# NEECDUINO_V22.net
KiCad netlist of a schematic drawn in EAGLE
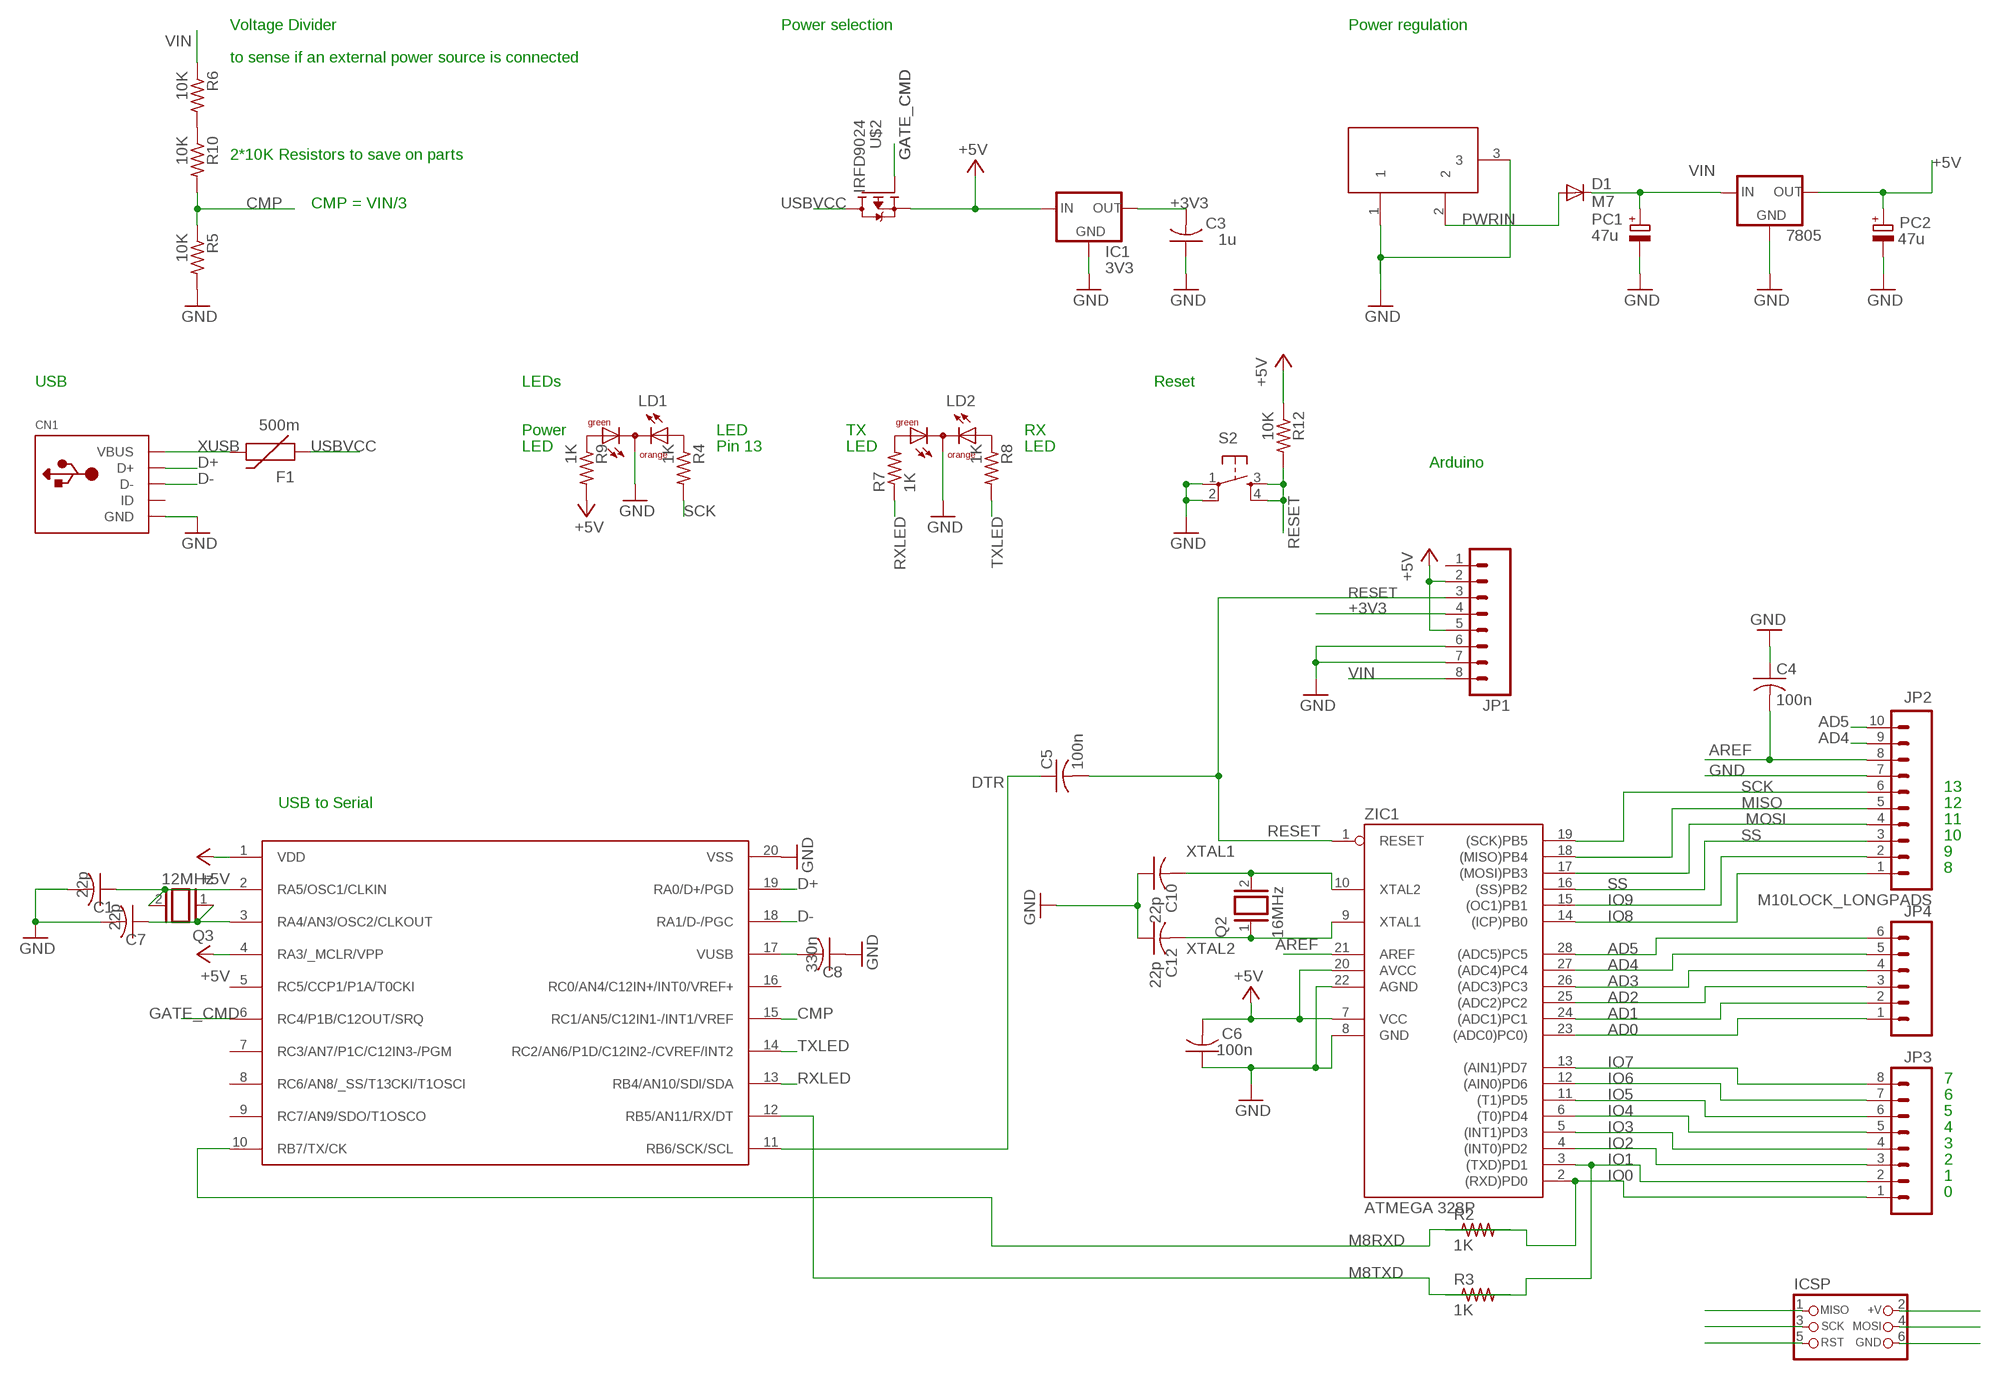
[diagram p0: schematic, sheet 1]

(export (version "E")
  (design (tool "Eeschema 10.0.6"))
  (components
    (comp (ref "7805")
      (value "78XXL")
      (footprint "eagle-import:78XXL")
      (libsource (lib "eagle-import") (part "78XXL"))
    )
    (comp (ref "C1")
      (value "22p")
      (footprint "eagle-import:C025-025X050")
      (libsource (lib "eagle-import") (part "C-US025-025X050"))
    )
    (comp (ref "C3")
      (value "1u")
      (footprint "eagle-import:C050-024X044")
      (libsource (lib "eagle-import") (part "C-US050-024X044"))
    )
    (comp (ref "C4")
      (value "100n")
      (footprint "eagle-import:C025-025X050")
      (libsource (lib "eagle-import") (part "C-US025-025X050"))
    )
    (comp (ref "C5")
      (value "100n")
      (footprint "eagle-import:C025-025X050")
      (libsource (lib "eagle-import") (part "C-US025-025X050"))
    )
    (comp (ref "C6")
      (value "100n")
      (footprint "eagle-import:C025-025X050")
      (libsource (lib "eagle-import") (part "C-US025-025X050"))
    )
    (comp (ref "C7")
      (value "22p")
      (footprint "eagle-import:C025-025X050")
      (libsource (lib "eagle-import") (part "C-US025-025X050"))
    )
    (comp (ref "C8")
      (value "330n")
      (footprint "eagle-import:C025-025X050")
      (libsource (lib "eagle-import") (part "C-US025-025X050"))
    )
    (comp (ref "C10")
      (value "22p")
      (footprint "eagle-import:C025-025X050")
      (libsource (lib "eagle-import") (part "C-US025-025X050"))
    )
    (comp (ref "C12")
      (value "22p")
      (footprint "eagle-import:C025-025X050")
      (libsource (lib "eagle-import") (part "C-US025-025X050"))
    )
    (comp (ref "CN1")
      (value "USBMOLEX")
      (footprint "eagle-import:USB-MINIB-THM-MOLEX")
      (libsource (lib "eagle-import") (part "USBMOLEX"))
    )
    (comp (ref "D1")
      (value "M7")
      (footprint "eagle-import:D-10")
      (libsource (lib "eagle-import") (part "DIODE-D-10"))
    )
    (comp (ref "F1")
      (value "500m")
      (footprint "eagle-import:PTC")
      (libsource (lib "eagle-import") (part "PTCPTH"))
    )
    (comp (ref "IC1")
      (value "3V3")
      (footprint "eagle-import:TO92-INLINE")
      (libsource (lib "eagle-import") (part "LP2950?"))
    )
    (comp (ref "ICSP")
      (value "CON_HEADER_PRG_AVR_ICSP")
      (footprint "eagle-import:HEADER_PRG_2X03")
      (libsource (lib "eagle-import") (part "CON_HEADER_PRG_AVR_ICSP"))
    )
    (comp (ref "JP1")
      (value "M08LOCK_LONGPADS")
      (footprint "eagle-import:1X08_LOCK_LONGPADS")
      (libsource (lib "eagle-import") (part "M08LOCK_LONGPADS"))
    )
    (comp (ref "JP2")
      (value "M10LOCK_LONGPADS")
      (footprint "eagle-import:1X10_LOCK_LONGPADS")
      (libsource (lib "eagle-import") (part "M10LOCK_LONGPADS"))
    )
    (comp (ref "JP3")
      (value "M08LOCK_LONGPADS")
      (footprint "eagle-import:1X08_LOCK_LONGPADS")
      (libsource (lib "eagle-import") (part "M08LOCK_LONGPADS"))
    )
    (comp (ref "JP4")
      (value "M06LOCK_LONGPADS")
      (footprint "eagle-import:1X06_LOCK_LONGPADS")
      (libsource (lib "eagle-import") (part "M06LOCK_LONGPADS"))
    )
    (comp (ref "LD1")
      (value "DUOLED-GO-C")
      (footprint "eagle-import:DUOLED-C-3MM")
      (libsource (lib "eagle-import") (part "DUOLED-GO-C"))
    )
    (comp (ref "LD2")
      (value "DUOLED-GO-C")
      (footprint "eagle-import:DUOLED-C-3MM")
      (libsource (lib "eagle-import") (part "DUOLED-GO-C"))
    )
    (comp (ref "PC1")
      (value "47u")
      (footprint "eagle-import:E2,5-5")
      (libsource (lib "eagle-import") (part "CPOL-EUE2.5-5"))
    )
    (comp (ref "PC2")
      (value "47u")
      (footprint "eagle-import:E2,5-5")
      (libsource (lib "eagle-import") (part "CPOL-EUE2.5-5"))
    )
    (comp (ref "Q2")
      (value "16MHz")
      (footprint "eagle-import:QS")
      (libsource (lib "eagle-import") (part "XTAL/S"))
    )
    (comp (ref "Q3")
      (value "12MHz")
      (footprint "eagle-import:QS")
      (libsource (lib "eagle-import") (part "XTAL/S"))
    )
    (comp (ref "R2")
      (value "1K")
      (footprint "eagle-import:0204_5")
      (libsource (lib "eagle-import") (part "R-US_0204/5"))
    )
    (comp (ref "R3")
      (value "1K")
      (footprint "eagle-import:0204_5")
      (libsource (lib "eagle-import") (part "R-US_0204/5"))
    )
    (comp (ref "R4")
      (value "1K")
      (footprint "eagle-import:0204_5")
      (libsource (lib "eagle-import") (part "R-US_0204/5"))
    )
    (comp (ref "R5")
      (value "10K")
      (footprint "eagle-import:0204_5")
      (libsource (lib "eagle-import") (part "R-US_0204/5"))
    )
    (comp (ref "R6")
      (value "10K")
      (footprint "eagle-import:0204_5")
      (libsource (lib "eagle-import") (part "R-US_0204/5"))
    )
    (comp (ref "R7")
      (value "1K")
      (footprint "eagle-import:0204_5")
      (libsource (lib "eagle-import") (part "R-US_0204/5"))
    )
    (comp (ref "R8")
      (value "1K")
      (footprint "eagle-import:0204_5")
      (libsource (lib "eagle-import") (part "R-US_0204/5"))
    )
    (comp (ref "R9")
      (value "1K")
      (footprint "eagle-import:0204_5")
      (libsource (lib "eagle-import") (part "R-US_0204/5"))
    )
    (comp (ref "R10")
      (value "10K")
      (footprint "eagle-import:0204_5")
      (libsource (lib "eagle-import") (part "R-US_0204/5"))
    )
    (comp (ref "R12")
      (value "10K")
      (footprint "eagle-import:0204_5")
      (libsource (lib "eagle-import") (part "R-US_0204/5"))
    )
    (comp (ref "S2")
      (value "TAC_SWITCHPTH")
      (footprint "eagle-import:TACTILE-PTH")
      (libsource (lib "eagle-import") (part "TAC_SWITCHPTH"))
    )
    (comp (ref "U$1")
      (value "PIC18F14K50")
      (footprint "eagle-import:DIL20")
      (libsource (lib "eagle-import") (part "PIC18XF1XK50"))
    )
    (comp (ref "U$2")
      (value "IRFD9024")
      (footprint "eagle-import:DIL04")
      (libsource (lib "eagle-import") (part "IRFD9024"))
    )
    (comp (ref "X1")
      (value "DC21MMX")
      (footprint "eagle-import:DC-21MM")
      (libsource (lib "eagle-import") (part "DC21MMX"))
    )
    (comp (ref "ZIC1")
      (value "ATMEGA 328P")
      (footprint "eagle-import:DIL28-3")
      (libsource (lib "eagle-import") (part "AT90S4433P"))
    )
  )
  (nets
    (net (code "1") (name "+5V") (class "Default")
      (node (ref "7805") (pin "OUT") (pinfunction "OUT_OUT") (pintype "passive"))
      (node (ref "C6") (pin "2") (pinfunction "2_2") (pintype "passive"))
      (node (ref "IC1") (pin "3") (pinfunction "IN_3") (pintype "input"))
      (node (ref "ICSP") (pin "2") (pinfunction "+V_2") (pintype "passive"))
      (node (ref "JP1") (pin "2") (pinfunction "2_2") (pintype "passive"))
      (node (ref "JP1") (pin "5") (pinfunction "5_5") (pintype "passive"))
      (node (ref "PC2") (pin "+") (pinfunction "+_+") (pintype "passive"))
      (node (ref "R12") (pin "1") (pinfunction "1_1") (pintype "passive"))
      (node (ref "R9") (pin "2") (pinfunction "2_2") (pintype "passive"))
      (node (ref "U$1") (pin "1") (pinfunction "VDD_1") (pintype "power_in"))
      (node (ref "U$1") (pin "4") (pinfunction "RA3/_MCLR/VPP_4") (pintype "bidirectional"))
      (node (ref "U$2") (pin "4") (pinfunction "S_4") (pintype "passive"))
      (node (ref "ZIC1") (pin "20") (pinfunction "AVCC_20") (pintype "power_in"))
      (node (ref "ZIC1") (pin "7") (pinfunction "VCC_7") (pintype "power_in"))
    )
    (net (code "2") (name "/+3V3") (class "Default")
      (node (ref "C3") (pin "2") (pinfunction "2_2") (pintype "passive"))
      (node (ref "IC1") (pin "1") (pinfunction "OUT_1") (pintype "passive"))
      (node (ref "JP1") (pin "4") (pinfunction "4_4") (pintype "passive"))
    )
    (net (code "3") (name "/AD0") (class "Default")
      (node (ref "JP4") (pin "1") (pinfunction "1_1") (pintype "passive"))
      (node (ref "ZIC1") (pin "23") (pinfunction "(ADC0)PC0)_23") (pintype "bidirectional"))
    )
    (net (code "4") (name "/AD1") (class "Default")
      (node (ref "JP4") (pin "2") (pinfunction "2_2") (pintype "passive"))
      (node (ref "ZIC1") (pin "24") (pinfunction "(ADC1)PC1_24") (pintype "bidirectional"))
    )
    (net (code "5") (name "/AD2") (class "Default")
      (node (ref "JP4") (pin "3") (pinfunction "3_3") (pintype "passive"))
      (node (ref "ZIC1") (pin "25") (pinfunction "(ADC2)PC2_25") (pintype "bidirectional"))
    )
    (net (code "6") (name "/AD3") (class "Default")
      (node (ref "JP4") (pin "4") (pinfunction "4_4") (pintype "passive"))
      (node (ref "ZIC1") (pin "26") (pinfunction "(ADC3)PC3_26") (pintype "bidirectional"))
    )
    (net (code "7") (name "/AD4") (class "Default")
      (node (ref "JP2") (pin "9") (pinfunction "9_9") (pintype "passive"))
      (node (ref "JP4") (pin "5") (pinfunction "5_5") (pintype "passive"))
      (node (ref "ZIC1") (pin "27") (pinfunction "(ADC4)PC4_27") (pintype "bidirectional"))
    )
    (net (code "8") (name "/AD5") (class "Default")
      (node (ref "JP2") (pin "10") (pinfunction "10_10") (pintype "passive"))
      (node (ref "JP4") (pin "6") (pinfunction "6_6") (pintype "passive"))
      (node (ref "ZIC1") (pin "28") (pinfunction "(ADC5)PC5_28") (pintype "bidirectional"))
    )
    (net (code "9") (name "/AREF") (class "Default")
      (node (ref "C4") (pin "2") (pinfunction "2_2") (pintype "passive"))
      (node (ref "JP2") (pin "8") (pinfunction "8_8") (pintype "passive"))
      (node (ref "ZIC1") (pin "21") (pinfunction "AREF_21") (pintype "passive"))
    )
    (net (code "10") (name "/CMP") (class "Default")
      (node (ref "R10") (pin "2") (pinfunction "2_2") (pintype "passive"))
      (node (ref "R5") (pin "1") (pinfunction "1_1") (pintype "passive"))
      (node (ref "U$1") (pin "15") (pinfunction "RC1/AN5/C12IN1-/INT1/VREF_15") (pintype "bidirectional"))
    )
    (net (code "11") (name "/D+") (class "Default")
      (node (ref "CN1") (pin "D+") (pinfunction "D+_D+") (pintype "bidirectional"))
      (node (ref "U$1") (pin "19") (pinfunction "RA0/D+/PGD_19") (pintype "bidirectional"))
    )
    (net (code "12") (name "/D-") (class "Default")
      (node (ref "CN1") (pin "D-") (pinfunction "D-_D-") (pintype "bidirectional"))
      (node (ref "U$1") (pin "18") (pinfunction "RA1/D-/PGC_18") (pintype "bidirectional"))
    )
    (net (code "13") (name "/DTR") (class "Default")
      (node (ref "C5") (pin "1") (pinfunction "1_1") (pintype "passive"))
      (node (ref "U$1") (pin "11") (pinfunction "RB6/SCK/SCL_11") (pintype "bidirectional"))
    )
    (net (code "14") (name "/GATE_CMD") (class "Default")
      (node (ref "U$1") (pin "6") (pinfunction "RC4/P1B/C12OUT/SRQ_6") (pintype "bidirectional"))
      (node (ref "U$2") (pin "3") (pinfunction "G_3") (pintype "passive"))
    )
    (net (code "15") (name "/IO0") (class "Default")
      (node (ref "JP3") (pin "1") (pinfunction "1_1") (pintype "passive"))
      (node (ref "R2") (pin "1") (pinfunction "1_1") (pintype "passive"))
      (node (ref "ZIC1") (pin "2") (pinfunction "(RXD)PD0_2") (pintype "bidirectional"))
    )
    (net (code "16") (name "/IO1") (class "Default")
      (node (ref "JP3") (pin "2") (pinfunction "2_2") (pintype "passive"))
      (node (ref "R3") (pin "1") (pinfunction "1_1") (pintype "passive"))
      (node (ref "ZIC1") (pin "3") (pinfunction "(TXD)PD1_3") (pintype "bidirectional"))
    )
    (net (code "17") (name "/IO2") (class "Default")
      (node (ref "JP3") (pin "3") (pinfunction "3_3") (pintype "passive"))
      (node (ref "ZIC1") (pin "4") (pinfunction "(INT0)PD2_4") (pintype "bidirectional"))
    )
    (net (code "18") (name "/IO3") (class "Default")
      (node (ref "JP3") (pin "4") (pinfunction "4_4") (pintype "passive"))
      (node (ref "ZIC1") (pin "5") (pinfunction "(INT1)PD3_5") (pintype "bidirectional"))
    )
    (net (code "19") (name "/IO4") (class "Default")
      (node (ref "JP3") (pin "5") (pinfunction "5_5") (pintype "passive"))
      (node (ref "ZIC1") (pin "6") (pinfunction "(T0)PD4_6") (pintype "bidirectional"))
    )
    (net (code "20") (name "/IO5") (class "Default")
      (node (ref "JP3") (pin "6") (pinfunction "6_6") (pintype "passive"))
      (node (ref "ZIC1") (pin "11") (pinfunction "(T1)PD5_11") (pintype "bidirectional"))
    )
    (net (code "21") (name "/IO6") (class "Default")
      (node (ref "JP3") (pin "7") (pinfunction "7_7") (pintype "passive"))
      (node (ref "ZIC1") (pin "12") (pinfunction "(AIN0)PD6_12") (pintype "bidirectional"))
    )
    (net (code "22") (name "/IO7") (class "Default")
      (node (ref "JP3") (pin "8") (pinfunction "8_8") (pintype "passive"))
      (node (ref "ZIC1") (pin "13") (pinfunction "(AIN1)PD7_13") (pintype "bidirectional"))
    )
    (net (code "23") (name "/IO8") (class "Default")
      (node (ref "JP2") (pin "1") (pinfunction "1_1") (pintype "passive"))
      (node (ref "ZIC1") (pin "14") (pinfunction "(ICP)PB0_14") (pintype "bidirectional"))
    )
    (net (code "24") (name "/IO9") (class "Default")
      (node (ref "JP2") (pin "2") (pinfunction "2_2") (pintype "passive"))
      (node (ref "ZIC1") (pin "15") (pinfunction "(OC1)PB1_15") (pintype "bidirectional"))
    )
    (net (code "25") (name "/M8RXD") (class "Default")
      (node (ref "R2") (pin "2") (pinfunction "2_2") (pintype "passive"))
      (node (ref "U$1") (pin "10") (pinfunction "RB7/TX/CK_10") (pintype "bidirectional"))
    )
    (net (code "26") (name "/M8TXD") (class "Default")
      (node (ref "R3") (pin "2") (pinfunction "2_2") (pintype "passive"))
      (node (ref "U$1") (pin "12") (pinfunction "RB5/AN11/RX/DT_12") (pintype "bidirectional"))
    )
    (net (code "27") (name "/MISO") (class "Default")
      (node (ref "ICSP") (pin "1") (pinfunction "MISO_1") (pintype "passive"))
      (node (ref "JP2") (pin "5") (pinfunction "5_5") (pintype "passive"))
      (node (ref "ZIC1") (pin "18") (pinfunction "(MISO)PB4_18") (pintype "bidirectional"))
    )
    (net (code "28") (name "/MOSI") (class "Default")
      (node (ref "ICSP") (pin "4") (pinfunction "MOSI_4") (pintype "passive"))
      (node (ref "JP2") (pin "4") (pinfunction "4_4") (pintype "passive"))
      (node (ref "ZIC1") (pin "17") (pinfunction "(MOSI)PB3_17") (pintype "bidirectional"))
    )
    (net (code "29") (name "/PWRIN") (class "Default")
      (node (ref "D1") (pin "A") (pinfunction "A_A") (pintype "passive"))
      (node (ref "X1") (pin "2") (pinfunction "2_2") (pintype "power_in"))
    )
    (net (code "30") (name "/RESET") (class "Default")
      (node (ref "C5") (pin "2") (pinfunction "2_2") (pintype "passive"))
      (node (ref "ICSP") (pin "5") (pinfunction "RST_5") (pintype "passive"))
      (node (ref "JP1") (pin "3") (pinfunction "3_3") (pintype "passive"))
      (node (ref "R12") (pin "2") (pinfunction "2_2") (pintype "passive"))
      (node (ref "S2") (pin "3") (pinfunction "3_3") (pintype "passive"))
      (node (ref "S2") (pin "4") (pinfunction "4_4") (pintype "passive"))
      (node (ref "ZIC1") (pin "1") (pinfunction "RESET_1") (pintype "input"))
    )
    (net (code "31") (name "/RXLED") (class "Default")
      (node (ref "R7") (pin "1") (pinfunction "1_1") (pintype "passive"))
      (node (ref "U$1") (pin "13") (pinfunction "RB4/AN10/SDI/SDA_13") (pintype "bidirectional"))
    )
    (net (code "32") (name "/SCK") (class "Default")
      (node (ref "ICSP") (pin "3") (pinfunction "SCK_3") (pintype "passive"))
      (node (ref "JP2") (pin "6") (pinfunction "6_6") (pintype "passive"))
      (node (ref "R4") (pin "2") (pinfunction "2_2") (pintype "passive"))
      (node (ref "ZIC1") (pin "19") (pinfunction "(SCK)PB5_19") (pintype "bidirectional"))
    )
    (net (code "33") (name "/SS") (class "Default")
      (node (ref "JP2") (pin "3") (pinfunction "3_3") (pintype "passive"))
      (node (ref "ZIC1") (pin "16") (pinfunction "(SS)PB2_16") (pintype "bidirectional"))
    )
    (net (code "34") (name "/TXLED") (class "Default")
      (node (ref "R8") (pin "2") (pinfunction "2_2") (pintype "passive"))
      (node (ref "U$1") (pin "14") (pinfunction "RC2/AN6/P1D/C12IN2-/CVREF/INT2_14") (pintype "bidirectional"))
    )
    (net (code "35") (name "/USBVCC") (class "Default")
      (node (ref "F1") (pin "P$1") (pinfunction "1_P$1") (pintype "bidirectional"))
      (node (ref "U$2") (pin "1") (pinfunction "D_1") (pintype "passive"))
      (node (ref "U$2") (pin "2") (pinfunction "D_2") (pintype "passive"))
    )
    (net (code "36") (name "/VIN") (class "Default")
      (node (ref "7805") (pin "IN") (pinfunction "IN_IN") (pintype "input"))
      (node (ref "D1") (pin "C") (pinfunction "C_C") (pintype "passive"))
      (node (ref "JP1") (pin "8") (pinfunction "8_8") (pintype "passive"))
      (node (ref "PC1") (pin "+") (pinfunction "+_+") (pintype "passive"))
      (node (ref "R6") (pin "1") (pinfunction "1_1") (pintype "passive"))
    )
    (net (code "37") (name "/XTAL1") (class "Default")
      (node (ref "C10") (pin "2") (pinfunction "2_2") (pintype "passive"))
      (node (ref "Q2") (pin "2") (pinfunction "2_2") (pintype "passive"))
      (node (ref "ZIC1") (pin "10") (pinfunction "XTAL2_10") (pintype "bidirectional"))
    )
    (net (code "38") (name "/XTAL2") (class "Default")
      (node (ref "C12") (pin "2") (pinfunction "2_2") (pintype "passive"))
      (node (ref "Q2") (pin "1") (pinfunction "1_1") (pintype "passive"))
      (node (ref "ZIC1") (pin "9") (pinfunction "XTAL1_9") (pintype "bidirectional"))
    )
    (net (code "39") (name "/XUSB") (class "Default")
      (node (ref "CN1") (pin "VBUS") (pinfunction "VBUS_VBUS") (pintype "power_in"))
      (node (ref "F1") (pin "P$2") (pinfunction "2_P$2") (pintype "bidirectional"))
    )
    (net (code "40") (name "GND") (class "Default")
      (node (ref "7805") (pin "GND") (pinfunction "GND_GND") (pintype "input"))
      (node (ref "C1") (pin "2") (pinfunction "2_2") (pintype "passive"))
      (node (ref "C10") (pin "1") (pinfunction "1_1") (pintype "passive"))
      (node (ref "C12") (pin "1") (pinfunction "1_1") (pintype "passive"))
      (node (ref "C3") (pin "1") (pinfunction "1_1") (pintype "passive"))
      (node (ref "C4") (pin "1") (pinfunction "1_1") (pintype "passive"))
      (node (ref "C6") (pin "1") (pinfunction "1_1") (pintype "passive"))
      (node (ref "C7") (pin "2") (pinfunction "2_2") (pintype "passive"))
      (node (ref "C8") (pin "1") (pinfunction "1_1") (pintype "passive"))
      (node (ref "CN1") (pin "GND") (pinfunction "GND_GND") (pintype "power_in"))
      (node (ref "IC1") (pin "2") (pinfunction "GND_2") (pintype "input"))
      (node (ref "ICSP") (pin "6") (pinfunction "GND_6") (pintype "passive"))
      (node (ref "JP1") (pin "6") (pinfunction "6_6") (pintype "passive"))
      (node (ref "JP1") (pin "7") (pinfunction "7_7") (pintype "passive"))
      (node (ref "JP2") (pin "7") (pinfunction "7_7") (pintype "passive"))
      (node (ref "LD1") (pin "C") (pinfunction "C_C") (pintype "passive"))
      (node (ref "LD2") (pin "C") (pinfunction "C_C") (pintype "passive"))
      (node (ref "PC1") (pin "-") (pinfunction "-_-") (pintype "passive"))
      (node (ref "PC2") (pin "-") (pinfunction "-_-") (pintype "passive"))
      (node (ref "R5") (pin "2") (pinfunction "2_2") (pintype "passive"))
      (node (ref "S2") (pin "1") (pinfunction "1_1") (pintype "passive"))
      (node (ref "S2") (pin "2") (pinfunction "2_2") (pintype "passive"))
      (node (ref "U$1") (pin "20") (pinfunction "VSS_20") (pintype "power_in"))
      (node (ref "X1") (pin "1") (pinfunction "1_1") (pintype "power_in"))
      (node (ref "X1") (pin "3") (pinfunction "3_3") (pintype "power_in"))
      (node (ref "ZIC1") (pin "22") (pinfunction "AGND_22") (pintype "power_in"))
      (node (ref "ZIC1") (pin "8") (pinfunction "GND_8") (pintype "power_in"))
    )
    (net (code "41") (name "Net-(LD1-AR)") (class "Default")
      (node (ref "LD1") (pin "AX") (pinfunction "AR_AX") (pintype "passive"))
      (node (ref "R9") (pin "1") (pinfunction "1_1") (pintype "passive"))
    )
    (net (code "42") (name "Net-(LD1-AY)") (class "Default")
      (node (ref "LD1") (pin "AR") (pinfunction "AY_AR") (pintype "passive"))
      (node (ref "R4") (pin "1") (pinfunction "1_1") (pintype "passive"))
    )
    (net (code "43") (name "Net-(LD2-AR)") (class "Default")
      (node (ref "LD2") (pin "AX") (pinfunction "AR_AX") (pintype "passive"))
      (node (ref "R7") (pin "2") (pinfunction "2_2") (pintype "passive"))
    )
    (net (code "44") (name "Net-(LD2-AY)") (class "Default")
      (node (ref "LD2") (pin "AR") (pinfunction "AY_AR") (pintype "passive"))
      (node (ref "R8") (pin "1") (pinfunction "1_1") (pintype "passive"))
    )
    (net (code "45") (name "Net-(R10-Pad1)") (class "Default")
      (node (ref "R10") (pin "1") (pinfunction "1_1") (pintype "passive"))
      (node (ref "R6") (pin "2") (pinfunction "2_2") (pintype "passive"))
    )
    (net (code "46") (name "Net-(U$1-RA4{slash}AN3{slash}OSC2{slash}CLKOUT)") (class "Default")
      (node (ref "C7") (pin "1") (pinfunction "1_1") (pintype "passive"))
      (node (ref "Q3") (pin "1") (pinfunction "1_1") (pintype "passive"))
      (node (ref "U$1") (pin "3") (pinfunction "RA4/AN3/OSC2/CLKOUT_3") (pintype "bidirectional"))
    )
    (net (code "47") (name "Net-(U$1-RA5{slash}OSC1{slash}CLKIN)") (class "Default")
      (node (ref "C1") (pin "1") (pinfunction "1_1") (pintype "passive"))
      (node (ref "Q3") (pin "2") (pinfunction "2_2") (pintype "passive"))
      (node (ref "U$1") (pin "2") (pinfunction "RA5/OSC1/CLKIN_2") (pintype "bidirectional"))
    )
    (net (code "48") (name "Net-(U$1-VUSB)") (class "Default")
      (node (ref "C8") (pin "2") (pinfunction "2_2") (pintype "passive"))
      (node (ref "U$1") (pin "17") (pinfunction "VUSB_17") (pintype "power_in"))
    )
    (net (code "49") (name "unconnected-(CN1-PadID)") (class "Default")
      (node (ref "CN1") (pin "ID") (pinfunction "ID_ID") (pintype "bidirectional"))
    )
    (net (code "50") (name "unconnected-(JP1-Pad1)") (class "Default")
      (node (ref "JP1") (pin "1") (pinfunction "1_1") (pintype "passive"))
    )
    (net (code "51") (name "unconnected-(U$1-RC0{slash}AN4{slash}C12IN+{slash}INT0{slash}VREF+-Pad16)") (class "Default")
      (node (ref "U$1") (pin "16") (pinfunction "RC0/AN4/C12IN+/INT0/VREF+_16") (pintype "bidirectional"))
    )
    (net (code "52") (name "unconnected-(U$1-RC3{slash}AN7{slash}P1C{slash}C12IN3-{slash}PGM-Pad7)") (class "Default")
      (node (ref "U$1") (pin "7") (pinfunction "RC3/AN7/P1C/C12IN3-/PGM_7") (pintype "bidirectional"))
    )
    (net (code "53") (name "unconnected-(U$1-RC5{slash}CCP1{slash}P1A{slash}T0CKI-Pad5)") (class "Default")
      (node (ref "U$1") (pin "5") (pinfunction "RC5/CCP1/P1A/T0CKI_5") (pintype "bidirectional"))
    )
    (net (code "54") (name "unconnected-(U$1-RC6{slash}AN8{slash}_SS{slash}T13CKI{slash}T1OSCI-Pad8)") (class "Default")
      (node (ref "U$1") (pin "8") (pinfunction "RC6/AN8/_SS/T13CKI/T1OSCI_8") (pintype "bidirectional"))
    )
    (net (code "55") (name "unconnected-(U$1-RC7{slash}AN9{slash}SDO{slash}T1OSCO-Pad9)") (class "Default")
      (node (ref "U$1") (pin "9") (pinfunction "RC7/AN9/SDO/T1OSCO_9") (pintype "bidirectional"))
    )
  )
)
